# Input1.net
KiCad netlist of a schematic drawn in Altium Designer
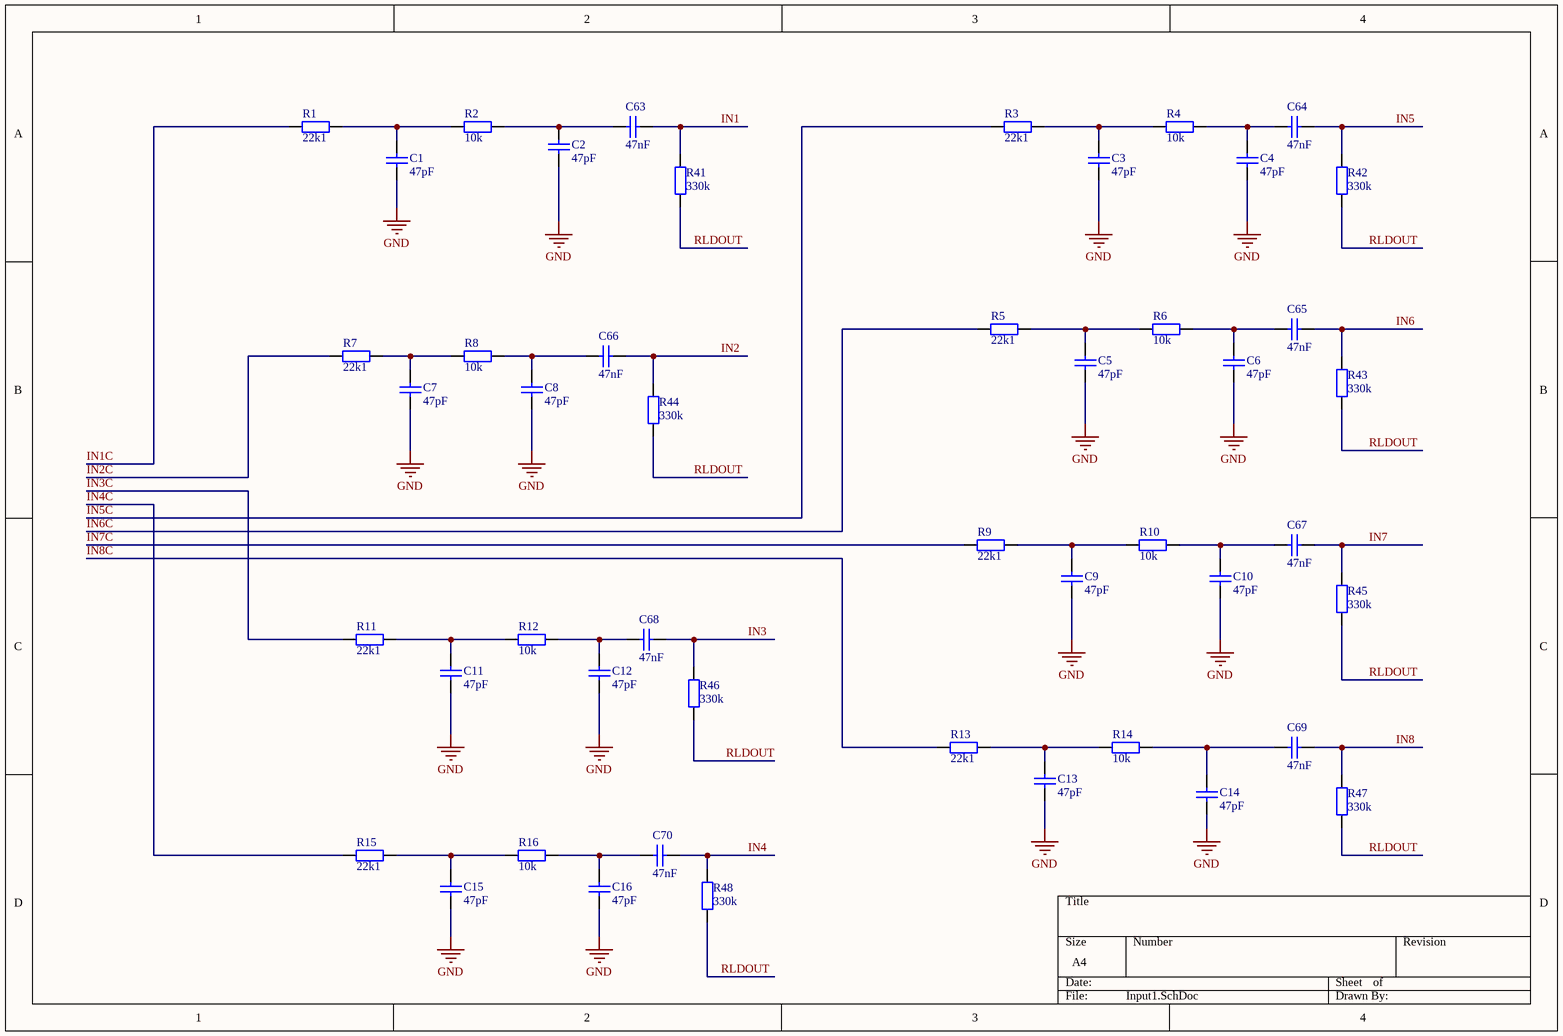
[diagram p0: Input1.SchDoc]

(export (version "E")
  (design (tool "Eeschema 10.0.6"))
  (components
    (comp (ref "C1")
      (value "47pF")
      (footprint "C0603")
      (description "Capacitor")
      (fields (field (name "PUBLISHER") "Altium Limited"))
      (libsource (lib "Miscellaneous Devices") (part "Cap"))
    )
    (comp (ref "C2")
      (value "47pF")
      (footprint "C0603")
      (description "Capacitor")
      (fields (field (name "PUBLISHER") "Altium Limited"))
      (libsource (lib "Miscellaneous Devices") (part "Cap"))
    )
    (comp (ref "C3")
      (value "47pF")
      (footprint "C0603")
      (description "Capacitor")
      (fields (field (name "PUBLISHER") "Altium Limited"))
      (libsource (lib "Miscellaneous Devices") (part "Cap"))
    )
    (comp (ref "C4")
      (value "47pF")
      (footprint "C0603")
      (description "Capacitor")
      (fields (field (name "PUBLISHER") "Altium Limited"))
      (libsource (lib "Miscellaneous Devices") (part "Cap"))
    )
    (comp (ref "C5")
      (value "47pF")
      (footprint "C0603")
      (description "Capacitor")
      (fields (field (name "PUBLISHER") "Altium Limited"))
      (libsource (lib "Miscellaneous Devices") (part "Cap"))
    )
    (comp (ref "C6")
      (value "47pF")
      (footprint "C0603")
      (description "Capacitor")
      (fields (field (name "PUBLISHER") "Altium Limited"))
      (libsource (lib "Miscellaneous Devices") (part "Cap"))
    )
    (comp (ref "C7")
      (value "47pF")
      (footprint "C0603")
      (description "Capacitor")
      (fields (field (name "PUBLISHER") "Altium Limited"))
      (libsource (lib "Miscellaneous Devices") (part "Cap"))
    )
    (comp (ref "C8")
      (value "47pF")
      (footprint "C0603")
      (description "Capacitor")
      (fields (field (name "PUBLISHER") "Altium Limited"))
      (libsource (lib "Miscellaneous Devices") (part "Cap"))
    )
    (comp (ref "C9")
      (value "47pF")
      (footprint "C0603")
      (description "Capacitor")
      (fields (field (name "PUBLISHER") "Altium Limited"))
      (libsource (lib "Miscellaneous Devices") (part "Cap"))
    )
    (comp (ref "C10")
      (value "47pF")
      (footprint "C0603")
      (description "Capacitor")
      (fields (field (name "PUBLISHER") "Altium Limited"))
      (libsource (lib "Miscellaneous Devices") (part "Cap"))
    )
    (comp (ref "C11")
      (value "47pF")
      (footprint "C0603")
      (description "Capacitor")
      (fields (field (name "PUBLISHER") "Altium Limited"))
      (libsource (lib "Miscellaneous Devices") (part "Cap"))
    )
    (comp (ref "C12")
      (value "47pF")
      (footprint "C0603")
      (description "Capacitor")
      (fields (field (name "PUBLISHER") "Altium Limited"))
      (libsource (lib "Miscellaneous Devices") (part "Cap"))
    )
    (comp (ref "C13")
      (value "47pF")
      (footprint "C0603")
      (description "Capacitor")
      (fields (field (name "PUBLISHER") "Altium Limited"))
      (libsource (lib "Miscellaneous Devices") (part "Cap"))
    )
    (comp (ref "C14")
      (value "47pF")
      (footprint "C0603")
      (description "Capacitor")
      (fields (field (name "PUBLISHER") "Altium Limited"))
      (libsource (lib "Miscellaneous Devices") (part "Cap"))
    )
    (comp (ref "C15")
      (value "47pF")
      (footprint "C0603")
      (description "Capacitor")
      (fields (field (name "PUBLISHER") "Altium Limited"))
      (libsource (lib "Miscellaneous Devices") (part "Cap"))
    )
    (comp (ref "C16")
      (value "47pF")
      (footprint "C0603")
      (description "Capacitor")
      (fields (field (name "PUBLISHER") "Altium Limited"))
      (libsource (lib "Miscellaneous Devices") (part "Cap"))
    )
    (comp (ref "C63")
      (value "47nF")
      (footprint "C0603")
      (description "Capacitor")
      (fields (field (name "PUBLISHER") "Altium Limited"))
      (libsource (lib "Miscellaneous Devices") (part "Cap"))
    )
    (comp (ref "C64")
      (value "47nF")
      (footprint "C0603")
      (description "Capacitor")
      (fields (field (name "PUBLISHER") "Altium Limited"))
      (libsource (lib "Miscellaneous Devices") (part "Cap"))
    )
    (comp (ref "C65")
      (value "47nF")
      (footprint "C0603")
      (description "Capacitor")
      (fields (field (name "PUBLISHER") "Altium Limited"))
      (libsource (lib "Miscellaneous Devices") (part "Cap"))
    )
    (comp (ref "C66")
      (value "47nF")
      (footprint "C0603")
      (description "Capacitor")
      (fields (field (name "PUBLISHER") "Altium Limited"))
      (libsource (lib "Miscellaneous Devices") (part "Cap"))
    )
    (comp (ref "C67")
      (value "47nF")
      (footprint "C0603")
      (description "Capacitor")
      (fields (field (name "PUBLISHER") "Altium Limited"))
      (libsource (lib "Miscellaneous Devices") (part "Cap"))
    )
    (comp (ref "C68")
      (value "47nF")
      (footprint "C0603")
      (description "Capacitor")
      (fields (field (name "PUBLISHER") "Altium Limited"))
      (libsource (lib "Miscellaneous Devices") (part "Cap"))
    )
    (comp (ref "C69")
      (value "47nF")
      (footprint "C0603")
      (description "Capacitor")
      (fields (field (name "PUBLISHER") "Altium Limited"))
      (libsource (lib "Miscellaneous Devices") (part "Cap"))
    )
    (comp (ref "C70")
      (value "47nF")
      (footprint "C0603")
      (description "Capacitor")
      (fields (field (name "PUBLISHER") "Altium Limited"))
      (libsource (lib "Miscellaneous Devices") (part "Cap"))
    )
    (comp (ref "R1")
      (value "22k1")
      (footprint "RES0603")
      (description "Resistor")
      (fields (field (name "PUBLISHER") "Altium Limited"))
      (libsource (lib "Miscellaneous Devices") (part "Res2"))
    )
    (comp (ref "R2")
      (value "10k")
      (footprint "RES0603")
      (description "Resistor")
      (fields (field (name "PUBLISHER") "Altium Limited"))
      (libsource (lib "Miscellaneous Devices") (part "Res2"))
    )
    (comp (ref "R3")
      (value "22k1")
      (footprint "RES0603")
      (description "Resistor")
      (fields (field (name "PUBLISHER") "Altium Limited"))
      (libsource (lib "Miscellaneous Devices") (part "Res2"))
    )
    (comp (ref "R4")
      (value "10k")
      (footprint "RES0603")
      (description "Resistor")
      (fields (field (name "PUBLISHER") "Altium Limited"))
      (libsource (lib "Miscellaneous Devices") (part "Res2"))
    )
    (comp (ref "R5")
      (value "22k1")
      (footprint "RES0603")
      (description "Resistor")
      (fields (field (name "PUBLISHER") "Altium Limited"))
      (libsource (lib "Miscellaneous Devices") (part "Res2"))
    )
    (comp (ref "R6")
      (value "10k")
      (footprint "RES0603")
      (description "Resistor")
      (fields (field (name "PUBLISHER") "Altium Limited"))
      (libsource (lib "Miscellaneous Devices") (part "Res2"))
    )
    (comp (ref "R7")
      (value "22k1")
      (footprint "RES0603")
      (description "Resistor")
      (fields (field (name "PUBLISHER") "Altium Limited"))
      (libsource (lib "Miscellaneous Devices") (part "Res2"))
    )
    (comp (ref "R8")
      (value "10k")
      (footprint "RES0603")
      (description "Resistor")
      (fields (field (name "PUBLISHER") "Altium Limited"))
      (libsource (lib "Miscellaneous Devices") (part "Res2"))
    )
    (comp (ref "R9")
      (value "22k1")
      (footprint "RES0603")
      (description "Resistor")
      (fields (field (name "PUBLISHER") "Altium Limited"))
      (libsource (lib "Miscellaneous Devices") (part "Res2"))
    )
    (comp (ref "R10")
      (value "10k")
      (footprint "RES0603")
      (description "Resistor")
      (fields (field (name "PUBLISHER") "Altium Limited"))
      (libsource (lib "Miscellaneous Devices") (part "Res2"))
    )
    (comp (ref "R11")
      (value "22k1")
      (footprint "RES0603")
      (description "Resistor")
      (fields (field (name "PUBLISHER") "Altium Limited"))
      (libsource (lib "Miscellaneous Devices") (part "Res2"))
    )
    (comp (ref "R12")
      (value "10k")
      (footprint "RES0603")
      (description "Resistor")
      (fields (field (name "PUBLISHER") "Altium Limited"))
      (libsource (lib "Miscellaneous Devices") (part "Res2"))
    )
    (comp (ref "R13")
      (value "22k1")
      (footprint "RES0603")
      (description "Resistor")
      (fields (field (name "PUBLISHER") "Altium Limited"))
      (libsource (lib "Miscellaneous Devices") (part "Res2"))
    )
    (comp (ref "R14")
      (value "10k")
      (footprint "RES0603")
      (description "Resistor")
      (fields (field (name "PUBLISHER") "Altium Limited"))
      (libsource (lib "Miscellaneous Devices") (part "Res2"))
    )
    (comp (ref "R15")
      (value "22k1")
      (footprint "RES0603")
      (description "Resistor")
      (fields (field (name "PUBLISHER") "Altium Limited"))
      (libsource (lib "Miscellaneous Devices") (part "Res2"))
    )
    (comp (ref "R16")
      (value "10k")
      (footprint "RES0603")
      (description "Resistor")
      (fields (field (name "PUBLISHER") "Altium Limited"))
      (libsource (lib "Miscellaneous Devices") (part "Res2"))
    )
    (comp (ref "R41")
      (value "330k")
      (footprint "RES0603")
      (description "Resistor")
      (fields (field (name "PUBLISHER") "Altium Limited"))
      (libsource (lib "") (part "Res2_1"))
    )
    (comp (ref "R42")
      (value "330k")
      (footprint "RES0603")
      (description "Resistor")
      (fields (field (name "PUBLISHER") "Altium Limited"))
      (libsource (lib "") (part "Res2_1"))
    )
    (comp (ref "R43")
      (value "330k")
      (footprint "RES0603")
      (description "Resistor")
      (fields (field (name "PUBLISHER") "Altium Limited"))
      (libsource (lib "") (part "Res2_1"))
    )
    (comp (ref "R44")
      (value "330k")
      (footprint "RES0603")
      (description "Resistor")
      (fields (field (name "PUBLISHER") "Altium Limited"))
      (libsource (lib "") (part "Res2_1"))
    )
    (comp (ref "R45")
      (value "330k")
      (footprint "RES0603")
      (description "Resistor")
      (fields (field (name "PUBLISHER") "Altium Limited"))
      (libsource (lib "") (part "Res2_1"))
    )
    (comp (ref "R46")
      (value "330k")
      (footprint "RES0603")
      (description "Resistor")
      (fields (field (name "PUBLISHER") "Altium Limited"))
      (libsource (lib "") (part "Res2_1"))
    )
    (comp (ref "R47")
      (value "330k")
      (footprint "RES0603")
      (description "Resistor")
      (fields (field (name "PUBLISHER") "Altium Limited"))
      (libsource (lib "") (part "Res2_1"))
    )
    (comp (ref "R48")
      (value "330k")
      (footprint "RES0603")
      (description "Resistor")
      (fields (field (name "PUBLISHER") "Altium Limited"))
      (libsource (lib "") (part "Res2_1"))
    )
  )
  (nets
    (net (code "1") (name "/IN1") (class "Default")
      (node (ref "C63") (pin "1") (pinfunction "1_1") (pintype "passive"))
      (node (ref "R41") (pin "2") (pinfunction "2_2") (pintype "passive"))
    )
    (net (code "2") (name "/IN1C") (class "Default")
      (node (ref "R1") (pin "1") (pinfunction "1_1") (pintype "passive"))
    )
    (net (code "3") (name "/IN2") (class "Default")
      (node (ref "C66") (pin "1") (pinfunction "1_1") (pintype "passive"))
      (node (ref "R44") (pin "2") (pinfunction "2_2") (pintype "passive"))
    )
    (net (code "4") (name "/IN2C") (class "Default")
      (node (ref "R7") (pin "1") (pinfunction "1_1") (pintype "passive"))
    )
    (net (code "5") (name "/IN3") (class "Default")
      (node (ref "C68") (pin "1") (pinfunction "1_1") (pintype "passive"))
      (node (ref "R46") (pin "2") (pinfunction "2_2") (pintype "passive"))
    )
    (net (code "6") (name "/IN3C") (class "Default")
      (node (ref "R11") (pin "1") (pinfunction "1_1") (pintype "passive"))
    )
    (net (code "7") (name "/IN4") (class "Default")
      (node (ref "C70") (pin "1") (pinfunction "1_1") (pintype "passive"))
      (node (ref "R48") (pin "2") (pinfunction "2_2") (pintype "passive"))
    )
    (net (code "8") (name "/IN4C") (class "Default")
      (node (ref "R15") (pin "1") (pinfunction "1_1") (pintype "passive"))
    )
    (net (code "9") (name "/IN5") (class "Default")
      (node (ref "C64") (pin "1") (pinfunction "1_1") (pintype "passive"))
      (node (ref "R42") (pin "2") (pinfunction "2_2") (pintype "passive"))
    )
    (net (code "10") (name "/IN5C") (class "Default")
      (node (ref "R3") (pin "1") (pinfunction "1_1") (pintype "passive"))
    )
    (net (code "11") (name "/IN6") (class "Default")
      (node (ref "C65") (pin "1") (pinfunction "1_1") (pintype "passive"))
      (node (ref "R43") (pin "2") (pinfunction "2_2") (pintype "passive"))
    )
    (net (code "12") (name "/IN6C") (class "Default")
      (node (ref "R5") (pin "1") (pinfunction "1_1") (pintype "passive"))
    )
    (net (code "13") (name "/IN7") (class "Default")
      (node (ref "C67") (pin "1") (pinfunction "1_1") (pintype "passive"))
      (node (ref "R45") (pin "2") (pinfunction "2_2") (pintype "passive"))
    )
    (net (code "14") (name "/IN7C") (class "Default")
      (node (ref "R9") (pin "1") (pinfunction "1_1") (pintype "passive"))
    )
    (net (code "15") (name "/IN8") (class "Default")
      (node (ref "C69") (pin "1") (pinfunction "1_1") (pintype "passive"))
      (node (ref "R47") (pin "2") (pinfunction "2_2") (pintype "passive"))
    )
    (net (code "16") (name "/IN8C") (class "Default")
      (node (ref "R13") (pin "1") (pinfunction "1_1") (pintype "passive"))
    )
    (net (code "17") (name "/RLDOUT") (class "Default")
      (node (ref "R41") (pin "1") (pinfunction "1_1") (pintype "passive"))
      (node (ref "R42") (pin "1") (pinfunction "1_1") (pintype "passive"))
      (node (ref "R43") (pin "1") (pinfunction "1_1") (pintype "passive"))
      (node (ref "R44") (pin "1") (pinfunction "1_1") (pintype "passive"))
      (node (ref "R45") (pin "1") (pinfunction "1_1") (pintype "passive"))
      (node (ref "R46") (pin "1") (pinfunction "1_1") (pintype "passive"))
      (node (ref "R47") (pin "1") (pinfunction "1_1") (pintype "passive"))
      (node (ref "R48") (pin "1") (pinfunction "1_1") (pintype "passive"))
    )
    (net (code "18") (name "GND") (class "Default")
      (node (ref "C1") (pin "1") (pinfunction "1_1") (pintype "passive"))
      (node (ref "C10") (pin "1") (pinfunction "1_1") (pintype "passive"))
      (node (ref "C11") (pin "1") (pinfunction "1_1") (pintype "passive"))
      (node (ref "C12") (pin "1") (pinfunction "1_1") (pintype "passive"))
      (node (ref "C13") (pin "1") (pinfunction "1_1") (pintype "passive"))
      (node (ref "C14") (pin "1") (pinfunction "1_1") (pintype "passive"))
      (node (ref "C15") (pin "1") (pinfunction "1_1") (pintype "passive"))
      (node (ref "C16") (pin "1") (pinfunction "1_1") (pintype "passive"))
      (node (ref "C2") (pin "1") (pinfunction "1_1") (pintype "passive"))
      (node (ref "C3") (pin "1") (pinfunction "1_1") (pintype "passive"))
      (node (ref "C4") (pin "1") (pinfunction "1_1") (pintype "passive"))
      (node (ref "C5") (pin "1") (pinfunction "1_1") (pintype "passive"))
      (node (ref "C6") (pin "1") (pinfunction "1_1") (pintype "passive"))
      (node (ref "C7") (pin "1") (pinfunction "1_1") (pintype "passive"))
      (node (ref "C8") (pin "1") (pinfunction "1_1") (pintype "passive"))
      (node (ref "C9") (pin "1") (pinfunction "1_1") (pintype "passive"))
    )
    (net (code "19") (name "Net-(C1-Pad2)") (class "Default")
      (node (ref "C1") (pin "2") (pinfunction "2_2") (pintype "passive"))
      (node (ref "R1") (pin "2") (pinfunction "2_2") (pintype "passive"))
      (node (ref "R2") (pin "1") (pinfunction "1_1") (pintype "passive"))
    )
    (net (code "20") (name "Net-(C2-Pad2)") (class "Default")
      (node (ref "C2") (pin "2") (pinfunction "2_2") (pintype "passive"))
      (node (ref "C63") (pin "2") (pinfunction "2_2") (pintype "passive"))
      (node (ref "R2") (pin "2") (pinfunction "2_2") (pintype "passive"))
    )
    (net (code "21") (name "Net-(C3-Pad2)") (class "Default")
      (node (ref "C3") (pin "2") (pinfunction "2_2") (pintype "passive"))
      (node (ref "R3") (pin "2") (pinfunction "2_2") (pintype "passive"))
      (node (ref "R4") (pin "1") (pinfunction "1_1") (pintype "passive"))
    )
    (net (code "22") (name "Net-(C4-Pad2)") (class "Default")
      (node (ref "C4") (pin "2") (pinfunction "2_2") (pintype "passive"))
      (node (ref "C64") (pin "2") (pinfunction "2_2") (pintype "passive"))
      (node (ref "R4") (pin "2") (pinfunction "2_2") (pintype "passive"))
    )
    (net (code "23") (name "Net-(C5-Pad2)") (class "Default")
      (node (ref "C5") (pin "2") (pinfunction "2_2") (pintype "passive"))
      (node (ref "R5") (pin "2") (pinfunction "2_2") (pintype "passive"))
      (node (ref "R6") (pin "1") (pinfunction "1_1") (pintype "passive"))
    )
    (net (code "24") (name "Net-(C6-Pad2)") (class "Default")
      (node (ref "C6") (pin "2") (pinfunction "2_2") (pintype "passive"))
      (node (ref "C65") (pin "2") (pinfunction "2_2") (pintype "passive"))
      (node (ref "R6") (pin "2") (pinfunction "2_2") (pintype "passive"))
    )
    (net (code "25") (name "Net-(C7-Pad2)") (class "Default")
      (node (ref "C7") (pin "2") (pinfunction "2_2") (pintype "passive"))
      (node (ref "R7") (pin "2") (pinfunction "2_2") (pintype "passive"))
      (node (ref "R8") (pin "1") (pinfunction "1_1") (pintype "passive"))
    )
    (net (code "26") (name "Net-(C9-Pad2)") (class "Default")
      (node (ref "C9") (pin "2") (pinfunction "2_2") (pintype "passive"))
      (node (ref "R10") (pin "1") (pinfunction "1_1") (pintype "passive"))
      (node (ref "R9") (pin "2") (pinfunction "2_2") (pintype "passive"))
    )
    (net (code "27") (name "Net-(C10-Pad2)") (class "Default")
      (node (ref "C10") (pin "2") (pinfunction "2_2") (pintype "passive"))
      (node (ref "C67") (pin "2") (pinfunction "2_2") (pintype "passive"))
      (node (ref "R10") (pin "2") (pinfunction "2_2") (pintype "passive"))
    )
    (net (code "28") (name "Net-(C11-Pad2)") (class "Default")
      (node (ref "C11") (pin "2") (pinfunction "2_2") (pintype "passive"))
      (node (ref "R11") (pin "2") (pinfunction "2_2") (pintype "passive"))
      (node (ref "R12") (pin "1") (pinfunction "1_1") (pintype "passive"))
    )
    (net (code "29") (name "Net-(C12-Pad2)") (class "Default")
      (node (ref "C12") (pin "2") (pinfunction "2_2") (pintype "passive"))
      (node (ref "C68") (pin "2") (pinfunction "2_2") (pintype "passive"))
      (node (ref "R12") (pin "2") (pinfunction "2_2") (pintype "passive"))
    )
    (net (code "30") (name "Net-(C13-Pad2)") (class "Default")
      (node (ref "C13") (pin "2") (pinfunction "2_2") (pintype "passive"))
      (node (ref "R13") (pin "2") (pinfunction "2_2") (pintype "passive"))
      (node (ref "R14") (pin "1") (pinfunction "1_1") (pintype "passive"))
    )
    (net (code "31") (name "Net-(C14-Pad2)") (class "Default")
      (node (ref "C14") (pin "2") (pinfunction "2_2") (pintype "passive"))
      (node (ref "C69") (pin "2") (pinfunction "2_2") (pintype "passive"))
      (node (ref "R14") (pin "2") (pinfunction "2_2") (pintype "passive"))
    )
    (net (code "32") (name "Net-(C15-Pad2)") (class "Default")
      (node (ref "C15") (pin "2") (pinfunction "2_2") (pintype "passive"))
      (node (ref "R15") (pin "2") (pinfunction "2_2") (pintype "passive"))
      (node (ref "R16") (pin "1") (pinfunction "1_1") (pintype "passive"))
    )
    (net (code "33") (name "Net-(C16-Pad2)") (class "Default")
      (node (ref "C16") (pin "2") (pinfunction "2_2") (pintype "passive"))
      (node (ref "C70") (pin "2") (pinfunction "2_2") (pintype "passive"))
      (node (ref "R16") (pin "2") (pinfunction "2_2") (pintype "passive"))
    )
    (net (code "34") (name "Net-(C66-Pad2)") (class "Default")
      (node (ref "C66") (pin "2") (pinfunction "2_2") (pintype "passive"))
      (node (ref "C8") (pin "2") (pinfunction "2_2") (pintype "passive"))
      (node (ref "R8") (pin "2") (pinfunction "2_2") (pintype "passive"))
    )
  )
)
